# CPU_LPC1776_SUP_PROG.net
KiCad netlist of a schematic drawn in Altium Designer
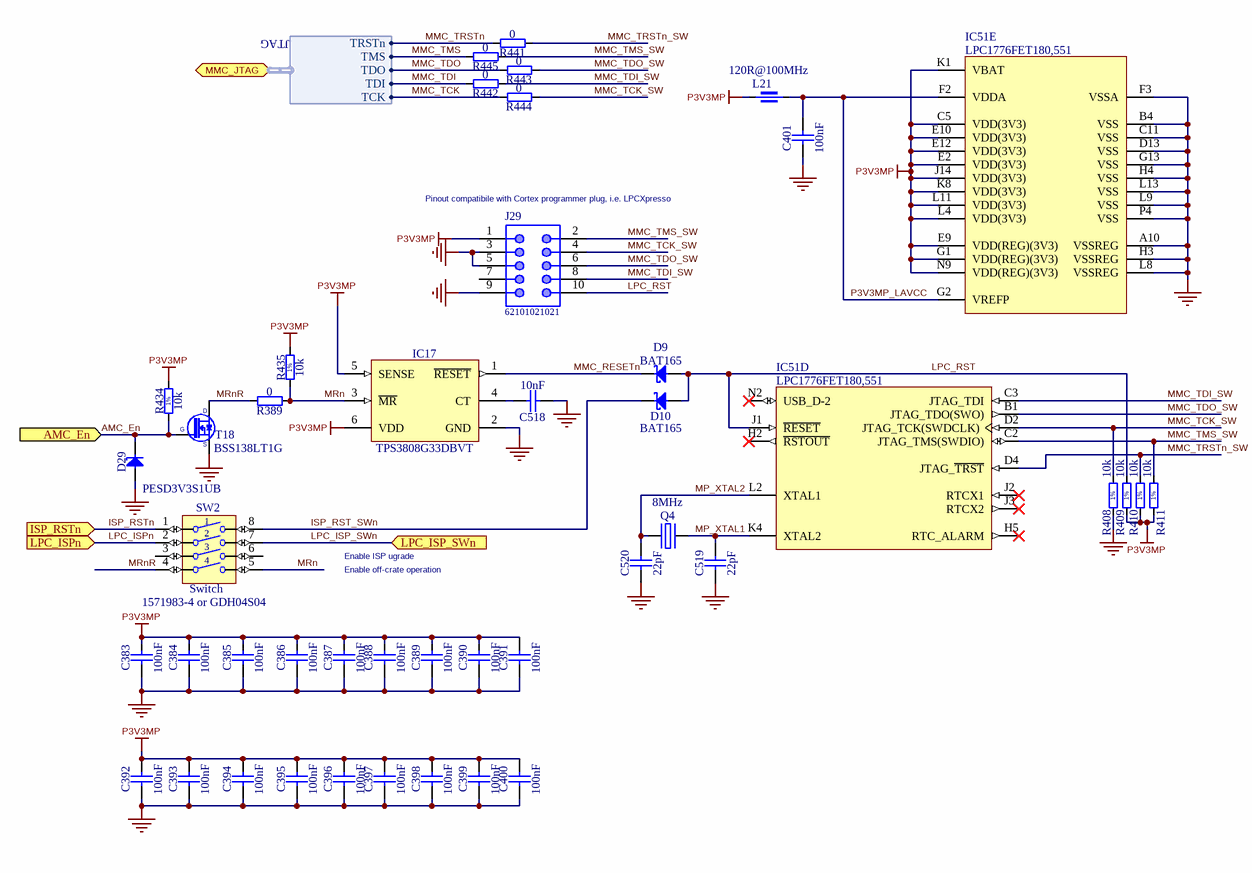
[diagram p0: CPU_LPC1776_SUP_PROG.SchDoc]

(export (version "E")
  (design (tool "Eeschema 10.0.6"))
  (components
    (comp (ref "C383")
      (value "100nF")
      (footprint "CAPC0603X33N")
      (description "Non-polarised capacitor")
      (fields
        (field (name "MANUFACTURER PART NUMBER") "CC0201_100NF_6.3V_10%_X5R")
        (field (name "MANUFACTURER") "GENERIC")
        (field (name "AUTHOR") "CERN DEM JLC")
      )
      (libsource (lib "Capacitors") (part "Capacitor - non polarized"))
    )
    (comp (ref "C384")
      (value "100nF")
      (footprint "CAPC0603X33N")
      (description "Non-polarised capacitor")
      (fields
        (field (name "MANUFACTURER PART NUMBER") "CC0201_100NF_6.3V_10%_X5R")
        (field (name "MANUFACTURER") "GENERIC")
        (field (name "AUTHOR") "CERN DEM JLC")
      )
      (libsource (lib "Capacitors") (part "Capacitor - non polarized"))
    )
    (comp (ref "C385")
      (value "100nF")
      (footprint "CAPC0603X33N")
      (description "Non-polarised capacitor")
      (fields
        (field (name "MANUFACTURER PART NUMBER") "CC0201_100NF_6.3V_10%_X5R")
        (field (name "MANUFACTURER") "GENERIC")
        (field (name "AUTHOR") "CERN DEM JLC")
      )
      (libsource (lib "Capacitors") (part "Capacitor - non polarized"))
    )
    (comp (ref "C386")
      (value "100nF")
      (footprint "CAPC0603X33N")
      (description "Non-polarised capacitor")
      (fields
        (field (name "MANUFACTURER PART NUMBER") "CC0201_100NF_6.3V_10%_X5R")
        (field (name "MANUFACTURER") "GENERIC")
        (field (name "AUTHOR") "CERN DEM JLC")
      )
      (libsource (lib "Capacitors") (part "Capacitor - non polarized"))
    )
    (comp (ref "C387")
      (value "100nF")
      (footprint "CAPC0603X33N")
      (description "Non-polarised capacitor")
      (fields
        (field (name "MANUFACTURER PART NUMBER") "CC0201_100NF_6.3V_10%_X5R")
        (field (name "MANUFACTURER") "GENERIC")
        (field (name "AUTHOR") "CERN DEM JLC")
      )
      (libsource (lib "Capacitors") (part "Capacitor - non polarized"))
    )
    (comp (ref "C388")
      (value "100nF")
      (footprint "CAPC0603X33N")
      (description "Non-polarised capacitor")
      (fields
        (field (name "MANUFACTURER PART NUMBER") "CC0201_100NF_6.3V_10%_X5R")
        (field (name "MANUFACTURER") "GENERIC")
        (field (name "AUTHOR") "CERN DEM JLC")
      )
      (libsource (lib "Capacitors") (part "Capacitor - non polarized"))
    )
    (comp (ref "C389")
      (value "100nF")
      (footprint "CAPC0603X33N")
      (description "Non-polarised capacitor")
      (fields
        (field (name "MANUFACTURER PART NUMBER") "CC0201_100NF_6.3V_10%_X5R")
        (field (name "MANUFACTURER") "GENERIC")
        (field (name "AUTHOR") "CERN DEM JLC")
      )
      (libsource (lib "Capacitors") (part "Capacitor - non polarized"))
    )
    (comp (ref "C390")
      (value "100nF")
      (footprint "CAPC0603X33N")
      (description "Non-polarised capacitor")
      (fields
        (field (name "MANUFACTURER PART NUMBER") "CC0201_100NF_6.3V_10%_X5R")
        (field (name "MANUFACTURER") "GENERIC")
        (field (name "AUTHOR") "CERN DEM JLC")
      )
      (libsource (lib "Capacitors") (part "Capacitor - non polarized"))
    )
    (comp (ref "C391")
      (value "100nF")
      (footprint "CAPC0603X33N")
      (description "Non-polarised capacitor")
      (fields
        (field (name "MANUFACTURER PART NUMBER") "CC0201_100NF_6.3V_10%_X5R")
        (field (name "MANUFACTURER") "GENERIC")
        (field (name "AUTHOR") "CERN DEM JLC")
      )
      (libsource (lib "Capacitors") (part "Capacitor - non polarized"))
    )
    (comp (ref "C392")
      (value "100nF")
      (footprint "CAPC0603X33N")
      (description "Non-polarised capacitor")
      (fields
        (field (name "MANUFACTURER PART NUMBER") "CC0201_100NF_6.3V_10%_X5R")
        (field (name "MANUFACTURER") "GENERIC")
        (field (name "AUTHOR") "CERN DEM JLC")
      )
      (libsource (lib "Capacitors") (part "Capacitor - non polarized"))
    )
    (comp (ref "C393")
      (value "100nF")
      (footprint "CAPC0603X33N")
      (description "Non-polarised capacitor")
      (fields
        (field (name "MANUFACTURER PART NUMBER") "CC0201_100NF_6.3V_10%_X5R")
        (field (name "MANUFACTURER") "GENERIC")
        (field (name "AUTHOR") "CERN DEM JLC")
      )
      (libsource (lib "Capacitors") (part "Capacitor - non polarized"))
    )
    (comp (ref "C394")
      (value "100nF")
      (footprint "CAPC0603X33N")
      (description "Non-polarised capacitor")
      (fields
        (field (name "MANUFACTURER PART NUMBER") "CC0201_100NF_6.3V_10%_X5R")
        (field (name "MANUFACTURER") "GENERIC")
        (field (name "AUTHOR") "CERN DEM JLC")
      )
      (libsource (lib "Capacitors") (part "Capacitor - non polarized"))
    )
    (comp (ref "C395")
      (value "100nF")
      (footprint "CAPC0603X33N")
      (description "Non-polarised capacitor")
      (fields
        (field (name "MANUFACTURER PART NUMBER") "CC0201_100NF_6.3V_10%_X5R")
        (field (name "MANUFACTURER") "GENERIC")
        (field (name "AUTHOR") "CERN DEM JLC")
      )
      (libsource (lib "Capacitors") (part "Capacitor - non polarized"))
    )
    (comp (ref "C396")
      (value "100nF")
      (footprint "CAPC0603X33N")
      (description "Non-polarised capacitor")
      (fields
        (field (name "MANUFACTURER PART NUMBER") "CC0201_100NF_6.3V_10%_X5R")
        (field (name "MANUFACTURER") "GENERIC")
        (field (name "AUTHOR") "CERN DEM JLC")
      )
      (libsource (lib "Capacitors") (part "Capacitor - non polarized"))
    )
    (comp (ref "C397")
      (value "100nF")
      (footprint "CAPC0603X33N")
      (description "Non-polarised capacitor")
      (fields
        (field (name "MANUFACTURER PART NUMBER") "CC0201_100NF_6.3V_10%_X5R")
        (field (name "MANUFACTURER") "GENERIC")
        (field (name "AUTHOR") "CERN DEM JLC")
      )
      (libsource (lib "Capacitors") (part "Capacitor - non polarized"))
    )
    (comp (ref "C398")
      (value "100nF")
      (footprint "CAPC0603X33N")
      (description "Non-polarised capacitor")
      (fields
        (field (name "MANUFACTURER PART NUMBER") "CC0201_100NF_6.3V_10%_X5R")
        (field (name "MANUFACTURER") "GENERIC")
        (field (name "AUTHOR") "CERN DEM JLC")
      )
      (libsource (lib "Capacitors") (part "Capacitor - non polarized"))
    )
    (comp (ref "C399")
      (value "100nF")
      (footprint "CAPC0603X33N")
      (description "Non-polarised capacitor")
      (fields
        (field (name "MANUFACTURER PART NUMBER") "CC0201_100NF_6.3V_10%_X5R")
        (field (name "MANUFACTURER") "GENERIC")
        (field (name "AUTHOR") "CERN DEM JLC")
      )
      (libsource (lib "Capacitors") (part "Capacitor - non polarized"))
    )
    (comp (ref "C400")
      (value "100nF")
      (footprint "CAPC0603X33N")
      (description "Non-polarised capacitor")
      (fields
        (field (name "MANUFACTURER PART NUMBER") "CC0201_100NF_6.3V_10%_X5R")
        (field (name "MANUFACTURER") "GENERIC")
        (field (name "AUTHOR") "CERN DEM JLC")
      )
      (libsource (lib "Capacitors") (part "Capacitor - non polarized"))
    )
    (comp (ref "C401")
      (value "100nF")
      (footprint "CAPC0603X33N")
      (description "Non-polarised capacitor")
      (fields
        (field (name "MANUFACTURER PART NUMBER") "CC0201_100NF_6.3V_10%_X5R")
        (field (name "MANUFACTURER") "GENERIC")
        (field (name "AUTHOR") "CERN DEM JLC")
      )
      (libsource (lib "Capacitors") (part "Capacitor - non polarized"))
    )
    (comp (ref "C518")
      (value "10nF")
      (footprint "CAPC1005X55N")
      (description "Non-polarised capacitor")
      (fields
        (field (name "MANUFACTURER PART NUMBER") "CC0402_10NF_16V_10%_X7R")
        (field (name "MANUFACTURER") "GENERIC")
        (field (name "AUTHOR") "CERN DEM JLC")
      )
      (libsource (lib "Capacitors") (part "Capacitor - non polarized"))
    )
    (comp (ref "C519")
      (value "22pF")
      (footprint "CAPC1005X55N")
      (description "Non-polarised capacitor")
      (fields
        (field (name "MANUFACTURER PART NUMBER") "CC0402_22PF_50V_5%_C0G")
        (field (name "MANUFACTURER") "GENERIC")
        (field (name "AUTHOR") "CERN DEM JLC")
      )
      (libsource (lib "Capacitors") (part "Capacitor - non polarized"))
    )
    (comp (ref "C520")
      (value "22pF")
      (footprint "CAPC1005X55N")
      (description "Non-polarised capacitor")
      (fields
        (field (name "MANUFACTURER PART NUMBER") "CC0402_22PF_50V_5%_C0G")
        (field (name "MANUFACTURER") "GENERIC")
        (field (name "AUTHOR") "CERN DEM JLC")
      )
      (libsource (lib "Capacitors") (part "Capacitor - non polarized"))
    )
    (comp (ref "D9")
      (value "BAT165")
      (footprint "SOD2512X110N")
      (description "Schottky Diode")
      (fields
        (field (name "MANUFACTURER") "INFINEON")
        (field (name "VOLTAGE") "40V")
        (field (name "AUTHOR") "CERN DEM JLC")
      )
      (libsource (lib "ICs And Semiconductors") (part "Diode Schottky"))
    )
    (comp (ref "D10")
      (value "BAT165")
      (footprint "SOD2512X110N")
      (description "Schottky Diode")
      (fields
        (field (name "MANUFACTURER") "INFINEON")
        (field (name "VOLTAGE") "40V")
        (field (name "AUTHOR") "CERN DEM JLC")
      )
      (libsource (lib "ICs And Semiconductors") (part "Diode Schottky"))
    )
    (comp (ref "D29")
      (value "PESD3V3S1UB")
      (footprint "SODFL1608X65N")
      (description "ESD protection diode")
      (fields
        (field (name "MANUFACTURER") "NXP SEMICONDUCTORS")
        (field (name "VOLTAGE") "3V3")
        (field (name "AUTHOR") "CERN DEM JLC")
      )
      (libsource (lib "ICs And Semiconductors") (part "Diode ESD"))
    )
    (comp (ref "IC17")
      (value "TPS3808G33DBVT")
      (footprint "SOT95P280X145-6N")
      (description "Low Quiescent Current, Programmable-Delay Supervisory Circuit")
      (fields (field (name "MANUFACTURER") "TEXAS INSTRUMENTS") (field (name "AUTHOR") "CERN DEM JLC"))
      (libsource (lib "ICs And Semiconductors") (part "TPS3808xxxDBV"))
    )
    (comp (ref "IC51")
      (value "LPC1776FET180,551")
      (footprint "BGA180C80P14X14_1200X1200X120")
      (fields (field (name "MANUFACTURER") "NXP SEMICONDUCTORS") (field (name "AUTHOR") "CERN DEM JMW"))
      (libsource (lib "ICs And Semiconductors") (part "LPC1776FET180,551"))
    )
    (comp (ref "J29")
      (value "62101021021")
      (footprint "62101021021")
      (description "SMT Vertical Pin Header WR-PHD, Pitch 1.27 mm, Dual Row, 10 pins")
      (fields (field (name "PUBLISHER") "Wurth Elektronik"))
      (libsource (lib "ALTIUM-WR-PHD_PIN_HEADER-rev18b") (part "62101021021"))
    )
    (comp (ref "L21")
      (value "120R@100MHz")
      (footprint "INDC1608X95N")
      (fields
        (field (name "MANUFACTURER PART NUMBER") "BLM18PG121SN1D")
        (field (name "MANUFACTURER") "MURATA")
        (field (name "PART NUMBER") "IND0603_MURATA_BLM18PG121SN1D")
        (field (name "AUTHOR") "CERN DEM BC")
      )
      (libsource (lib "Inductors & Transformers") (part "Ferrite Bead"))
    )
    (comp (ref "Q4")
      (value "8MHz")
      (footprint "XTAL_TXC_7A")
      (description "Quartz Crystal")
      (fields
        (field (name "MANUFACTURER PART NUMBER") "7A-8.000MAAE-T")
        (field (name "MANUFACTURER") "TXC CORPORATION")
        (field (name "AUTHOR") "CERN DEM JLC")
      )
      (libsource (lib "ICs And Semiconductors") (part "Quartz Crystal"))
    )
    (comp (ref "R389")
      (value "0")
      (footprint "RESC1005X40N")
      (description "Resistor")
      (fields
        (field (name "MANUFACTURER PART NUMBER") "R0402_0R_JUMPER")
        (field (name "MANUFACTURER") "GENERIC")
        (field (name "AUTHOR") "CERN DEM JLC")
      )
      (libsource (lib "Resistors") (part "Resistor"))
    )
    (comp (ref "R408")
      (value "10k")
      (footprint "RESC1005X40N")
      (description "Resistor - 1%")
      (fields
        (field (name "MANUFACTURER PART NUMBER") "R0402_10K_1%_0.0625W_100PPM")
        (field (name "MANUFACTURER") "GENERIC")
        (field (name "AUTHOR") "CERN DEM JLC")
      )
      (libsource (lib "Resistors") (part "Resistor - 1%"))
    )
    (comp (ref "R409")
      (value "10k")
      (footprint "RESC1005X40N")
      (description "Resistor - 1%")
      (fields
        (field (name "MANUFACTURER PART NUMBER") "R0402_10K_1%_0.0625W_100PPM")
        (field (name "MANUFACTURER") "GENERIC")
        (field (name "AUTHOR") "CERN DEM JLC")
      )
      (libsource (lib "Resistors") (part "Resistor - 1%"))
    )
    (comp (ref "R410")
      (value "10k")
      (footprint "RESC1005X40N")
      (description "Resistor - 1%")
      (fields
        (field (name "MANUFACTURER PART NUMBER") "R0402_10K_1%_0.0625W_100PPM")
        (field (name "MANUFACTURER") "GENERIC")
        (field (name "AUTHOR") "CERN DEM JLC")
      )
      (libsource (lib "Resistors") (part "Resistor - 1%"))
    )
    (comp (ref "R411")
      (value "10k")
      (footprint "RESC1005X40N")
      (description "Resistor - 1%")
      (fields
        (field (name "MANUFACTURER PART NUMBER") "R0402_10K_1%_0.0625W_100PPM")
        (field (name "MANUFACTURER") "GENERIC")
        (field (name "AUTHOR") "CERN DEM JLC")
      )
      (libsource (lib "Resistors") (part "Resistor - 1%"))
    )
    (comp (ref "R434")
      (value "10k")
      (footprint "RESC1005X40N")
      (description "Resistor - 1%")
      (fields
        (field (name "MANUFACTURER PART NUMBER") "R0402_10K_1%_0.0625W_100PPM")
        (field (name "MANUFACTURER") "GENERIC")
        (field (name "AUTHOR") "CERN DEM JLC")
      )
      (libsource (lib "Resistors") (part "Resistor - 1%"))
    )
    (comp (ref "R435")
      (value "10k")
      (footprint "RESC1005X40N")
      (description "Resistor - 1%")
      (fields
        (field (name "MANUFACTURER PART NUMBER") "R0402_10K_1%_0.0625W_100PPM")
        (field (name "MANUFACTURER") "GENERIC")
        (field (name "AUTHOR") "CERN DEM JLC")
      )
      (libsource (lib "Resistors") (part "Resistor - 1%"))
    )
    (comp (ref "R441")
      (value "0")
      (footprint "RESC1005X40N")
      (description "Resistor")
      (fields
        (field (name "MANUFACTURER PART NUMBER") "R0402_0R_JUMPER")
        (field (name "MANUFACTURER") "GENERIC")
        (field (name "AUTHOR") "CERN DEM JLC")
      )
      (libsource (lib "Resistors") (part "Resistor"))
    )
    (comp (ref "R442")
      (value "0")
      (footprint "RESC1005X40N")
      (description "Resistor")
      (fields
        (field (name "MANUFACTURER PART NUMBER") "R0402_0R_JUMPER")
        (field (name "MANUFACTURER") "GENERIC")
        (field (name "AUTHOR") "CERN DEM JLC")
      )
      (libsource (lib "Resistors") (part "Resistor"))
    )
    (comp (ref "R443")
      (value "0")
      (footprint "RESC1005X40N")
      (description "Resistor")
      (fields
        (field (name "MANUFACTURER PART NUMBER") "R0402_0R_JUMPER")
        (field (name "MANUFACTURER") "GENERIC")
        (field (name "AUTHOR") "CERN DEM JLC")
      )
      (libsource (lib "Resistors") (part "Resistor"))
    )
    (comp (ref "R444")
      (value "0")
      (footprint "RESC1005X40N")
      (description "Resistor")
      (fields
        (field (name "MANUFACTURER PART NUMBER") "R0402_0R_JUMPER")
        (field (name "MANUFACTURER") "GENERIC")
        (field (name "AUTHOR") "CERN DEM JLC")
      )
      (libsource (lib "Resistors") (part "Resistor"))
    )
    (comp (ref "R445")
      (value "0")
      (footprint "RESC1005X40N")
      (description "Resistor")
      (fields
        (field (name "MANUFACTURER PART NUMBER") "R0402_0R_JUMPER")
        (field (name "MANUFACTURER") "GENERIC")
        (field (name "AUTHOR") "CERN DEM JLC")
      )
      (libsource (lib "Resistors") (part "Resistor"))
    )
    (comp (ref "SW2")
      (value "Switch")
      (footprint "SW_TYCO_1571983-4")
      (description "4 Ways SPST DIP Switch")
      (fields
        (field (name "MANUFACTURER PART NUMBER") "1571983-4 or GDH04S04")
        (field (name "MANUFACTURER") "TYCO")
        (field (name "PART NUMBER") "SW_TYCO_1571983-4")
        (field (name "AUTHOR") "CERN DEM JLC")
      )
      (libsource (lib "Eletro-mechanical") (part "SW 4x SPST DIP Switch"))
    )
    (comp (ref "T18")
      (value "BSS138LT1G")
      (footprint "SOT95P240X110-3N")
      (description "N-CHANNEL MOSFET WITH DIODE")
      (fields (field (name "MANUFACTURER") "ON SEMICONDUCTOR") (field (name "AUTHOR") "CERN DEM JLC"))
      (libsource (lib "ICs And Semiconductors") (part "N-MOSFET-D 1G 2S 3D"))
    )
  )
  (nets
    (net (code "2") (name "/AMC_En") (class "Default")
      (node (ref "D29") (pin "1") (pinfunction "C_1") (pintype "passive"))
      (node (ref "R434") (pin "1") (pinfunction "1_1") (pintype "passive"))
      (node (ref "T18") (pin "1") (pinfunction "G_1") (pintype "passive"))
    )
    (net (code "3") (name "/ISP_RST_SWn") (class "Default")
      (node (ref "D10") (pin "1") (pinfunction "C_1") (pintype "passive"))
      (node (ref "SW2") (pin "8") (pinfunction "8_8") (pintype "bidirectional"))
    )
    (net (code "4") (name "/ISP_RSTn") (class "Default")
      (node (ref "SW2") (pin "1") (pinfunction "1_1") (pintype "bidirectional"))
    )
    (net (code "5") (name "/LPC_ISP_SWn") (class "Default")
      (node (ref "SW2") (pin "7") (pinfunction "7_7") (pintype "bidirectional"))
    )
    (net (code "6") (name "/LPC_ISPn") (class "Default")
      (node (ref "SW2") (pin "2") (pinfunction "2_2") (pintype "bidirectional"))
    )
    (net (code "7") (name "/LPC_RST") (class "Default")
      (node (ref "D10") (pin "2") (pinfunction "A_2") (pintype "passive"))
      (node (ref "D9") (pin "2") (pinfunction "A_2") (pintype "passive"))
      (node (ref "IC51") (pin "J1") (pinfunction "~{RESET}_J1") (pintype "input"))
      (node (ref "J29") (pin "10") (pinfunction "10_10") (pintype "passive"))
      (node (ref "R409") (pin "2") (pinfunction "2_2") (pintype "passive"))
    )
    (net (code "8") (name "/MMC_RESETn") (class "Default")
      (node (ref "D9") (pin "1") (pinfunction "C_1") (pintype "passive"))
      (node (ref "IC17") (pin "1") (pinfunction "~{RESET}_1") (pintype "output"))
    )
    (net (code "9") (name "/MMC_TCK") (class "Default")
      (node (ref "R444") (pin "2") (pinfunction "2_2") (pintype "passive"))
    )
    (net (code "10") (name "/MMC_TCK_SW") (class "Default")
      (node (ref "IC51") (pin "D2") (pinfunction "JTAG_TCK(SWDCLK)_D2") (pintype "input"))
      (node (ref "J29") (pin "4") (pinfunction "4_4") (pintype "passive"))
      (node (ref "R408") (pin "2") (pinfunction "2_2") (pintype "passive"))
      (node (ref "R444") (pin "1") (pinfunction "1_1") (pintype "passive"))
    )
    (net (code "11") (name "/MMC_TDI") (class "Default")
      (node (ref "R442") (pin "2") (pinfunction "2_2") (pintype "passive"))
    )
    (net (code "12") (name "/MMC_TDI_SW") (class "Default")
      (node (ref "IC51") (pin "C3") (pinfunction "JTAG_TDI_C3") (pintype "input"))
      (node (ref "J29") (pin "8") (pinfunction "8_8") (pintype "passive"))
      (node (ref "R442") (pin "1") (pinfunction "1_1") (pintype "passive"))
    )
    (net (code "13") (name "/MMC_TDO") (class "Default")
      (node (ref "R443") (pin "2") (pinfunction "2_2") (pintype "passive"))
    )
    (net (code "14") (name "/MMC_TDO_SW") (class "Default")
      (node (ref "IC51") (pin "B1") (pinfunction "JTAG_TDO(SWO)_B1") (pintype "output"))
      (node (ref "J29") (pin "6") (pinfunction "6_6") (pintype "passive"))
      (node (ref "R443") (pin "1") (pinfunction "1_1") (pintype "passive"))
    )
    (net (code "15") (name "/MMC_TMS") (class "Default")
      (node (ref "R445") (pin "2") (pinfunction "2_2") (pintype "passive"))
    )
    (net (code "16") (name "/MMC_TMS_SW") (class "Default")
      (node (ref "IC51") (pin "C2") (pinfunction "JTAG_TMS(SWDIO)_C2") (pintype "bidirectional"))
      (node (ref "J29") (pin "2") (pinfunction "2_2") (pintype "passive"))
      (node (ref "R411") (pin "2") (pinfunction "2_2") (pintype "passive"))
      (node (ref "R445") (pin "1") (pinfunction "1_1") (pintype "passive"))
    )
    (net (code "17") (name "/MMC_TRSTn") (class "Default")
      (node (ref "R441") (pin "2") (pinfunction "2_2") (pintype "passive"))
    )
    (net (code "18") (name "/MMC_TRSTn_SW") (class "Default")
      (node (ref "IC51") (pin "D4") (pinfunction "JTAG_~{TRST}_D4") (pintype "input"))
      (node (ref "R410") (pin "2") (pinfunction "2_2") (pintype "passive"))
      (node (ref "R441") (pin "1") (pinfunction "1_1") (pintype "passive"))
    )
    (net (code "19") (name "/MP_XTAL1") (class "Default")
      (node (ref "C519") (pin "2") (pinfunction "2_2") (pintype "passive"))
      (node (ref "IC51") (pin "K4") (pinfunction "XTAL2_K4") (pintype "passive"))
      (node (ref "Q4") (pin "2") (pinfunction "OSC2_2") (pintype "passive"))
    )
    (net (code "20") (name "/MP_XTAL2") (class "Default")
      (node (ref "C520") (pin "2") (pinfunction "2_2") (pintype "passive"))
      (node (ref "IC51") (pin "L2") (pinfunction "XTAL1_L2") (pintype "passive"))
      (node (ref "Q4") (pin "1") (pinfunction "OSC1_1") (pintype "passive"))
    )
    (net (code "21") (name "/MRn") (class "Default")
      (node (ref "IC17") (pin "3") (pinfunction "~{MR}_3") (pintype "input"))
      (node (ref "R389") (pin "1") (pinfunction "1_1") (pintype "passive"))
      (node (ref "R435") (pin "1") (pinfunction "1_1") (pintype "passive"))
      (node (ref "SW2") (pin "5") (pinfunction "5_5") (pintype "bidirectional"))
    )
    (net (code "22") (name "/MRnR") (class "Default")
      (node (ref "R389") (pin "2") (pinfunction "2_2") (pintype "passive"))
      (node (ref "SW2") (pin "4") (pinfunction "4_4") (pintype "bidirectional"))
      (node (ref "T18") (pin "3") (pinfunction "D_3") (pintype "passive"))
    )
    (net (code "23") (name "/P3V3MP_LAVCC") (class "Default")
      (node (ref "C401") (pin "1") (pinfunction "1_1") (pintype "passive"))
      (node (ref "IC51") (pin "F2") (pinfunction "VDDA_F2") (pintype "power_in"))
      (node (ref "IC51") (pin "G2") (pinfunction "VREFP_G2") (pintype "power_in"))
      (node (ref "L21") (pin "1") (pinfunction "1_1") (pintype "passive"))
    )
    (net (code "25") (name "GND") (class "Default")
      (node (ref "C383") (pin "2") (pinfunction "2_2") (pintype "passive"))
      (node (ref "C384") (pin "2") (pinfunction "2_2") (pintype "passive"))
      (node (ref "C385") (pin "2") (pinfunction "2_2") (pintype "passive"))
      (node (ref "C386") (pin "2") (pinfunction "2_2") (pintype "passive"))
      (node (ref "C387") (pin "2") (pinfunction "2_2") (pintype "passive"))
      (node (ref "C388") (pin "2") (pinfunction "2_2") (pintype "passive"))
      (node (ref "C389") (pin "2") (pinfunction "2_2") (pintype "passive"))
      (node (ref "C390") (pin "2") (pinfunction "2_2") (pintype "passive"))
      (node (ref "C391") (pin "2") (pinfunction "2_2") (pintype "passive"))
      (node (ref "C392") (pin "2") (pinfunction "2_2") (pintype "passive"))
      (node (ref "C393") (pin "2") (pinfunction "2_2") (pintype "passive"))
      (node (ref "C394") (pin "2") (pinfunction "2_2") (pintype "passive"))
      (node (ref "C395") (pin "2") (pinfunction "2_2") (pintype "passive"))
      (node (ref "C396") (pin "2") (pinfunction "2_2") (pintype "passive"))
      (node (ref "C397") (pin "2") (pinfunction "2_2") (pintype "passive"))
      (node (ref "C398") (pin "2") (pinfunction "2_2") (pintype "passive"))
      (node (ref "C399") (pin "2") (pinfunction "2_2") (pintype "passive"))
      (node (ref "C400") (pin "2") (pinfunction "2_2") (pintype "passive"))
      (node (ref "C401") (pin "2") (pinfunction "2_2") (pintype "passive"))
      (node (ref "C518") (pin "1") (pinfunction "1_1") (pintype "passive"))
      (node (ref "C519") (pin "1") (pinfunction "1_1") (pintype "passive"))
      (node (ref "C520") (pin "1") (pinfunction "1_1") (pintype "passive"))
      (node (ref "D29") (pin "2") (pinfunction "A_2") (pintype "passive"))
      (node (ref "IC17") (pin "2") (pinfunction "GND_2") (pintype "power_in"))
      (node (ref "IC51") (pin "A10") (pinfunction "VSSREG_A10") (pintype "power_in"))
      (node (ref "IC51") (pin "B4") (pinfunction "VSS_B4") (pintype "power_in"))
      (node (ref "IC51") (pin "C11") (pinfunction "VSS_C11") (pintype "power_in"))
      (node (ref "IC51") (pin "D13") (pinfunction "VSS_D13") (pintype "power_in"))
      (node (ref "IC51") (pin "F3") (pinfunction "VSSA_F3") (pintype "power_in"))
      (node (ref "IC51") (pin "G13") (pinfunction "VSS_G13") (pintype "power_in"))
      (node (ref "IC51") (pin "H3") (pinfunction "VSSREG_H3") (pintype "power_in"))
      (node (ref "IC51") (pin "H4") (pinfunction "VSS_H4") (pintype "power_in"))
      (node (ref "IC51") (pin "L13") (pinfunction "VSS_L13") (pintype "power_in"))
      (node (ref "IC51") (pin "L8") (pinfunction "VSSREG_L8") (pintype "power_in"))
      (node (ref "IC51") (pin "L9") (pinfunction "VSS_L9") (pintype "power_in"))
      (node (ref "IC51") (pin "P4") (pinfunction "VSS_P4") (pintype "power_in"))
      (node (ref "J29") (pin "3") (pinfunction "3_3") (pintype "passive"))
      (node (ref "J29") (pin "5") (pinfunction "5_5") (pintype "passive"))
      (node (ref "J29") (pin "9") (pinfunction "9_9") (pintype "passive"))
      (node (ref "R408") (pin "1") (pinfunction "1_1") (pintype "passive"))
      (node (ref "T18") (pin "2") (pinfunction "S_2") (pintype "passive"))
    )
    (net (code "26") (name "Net-(IC17-CT)") (class "Default")
      (node (ref "C518") (pin "2") (pinfunction "2_2") (pintype "passive"))
      (node (ref "IC17") (pin "4") (pinfunction "CT_4") (pintype "passive"))
    )
    (net (code "27") (name "P3V3MP") (class "Default")
      (node (ref "C383") (pin "1") (pinfunction "1_1") (pintype "passive"))
      (node (ref "C384") (pin "1") (pinfunction "1_1") (pintype "passive"))
      (node (ref "C385") (pin "1") (pinfunction "1_1") (pintype "passive"))
      (node (ref "C386") (pin "1") (pinfunction "1_1") (pintype "passive"))
      (node (ref "C387") (pin "1") (pinfunction "1_1") (pintype "passive"))
      (node (ref "C388") (pin "1") (pinfunction "1_1") (pintype "passive"))
      (node (ref "C389") (pin "1") (pinfunction "1_1") (pintype "passive"))
      (node (ref "C390") (pin "1") (pinfunction "1_1") (pintype "passive"))
      (node (ref "C391") (pin "1") (pinfunction "1_1") (pintype "passive"))
      (node (ref "C392") (pin "1") (pinfunction "1_1") (pintype "passive"))
      (node (ref "C393") (pin "1") (pinfunction "1_1") (pintype "passive"))
      (node (ref "C394") (pin "1") (pinfunction "1_1") (pintype "passive"))
      (node (ref "C395") (pin "1") (pinfunction "1_1") (pintype "passive"))
      (node (ref "C396") (pin "1") (pinfunction "1_1") (pintype "passive"))
      (node (ref "C397") (pin "1") (pinfunction "1_1") (pintype "passive"))
      (node (ref "C398") (pin "1") (pinfunction "1_1") (pintype "passive"))
      (node (ref "C399") (pin "1") (pinfunction "1_1") (pintype "passive"))
      (node (ref "C400") (pin "1") (pinfunction "1_1") (pintype "passive"))
      (node (ref "IC17") (pin "5") (pinfunction "SENSE_5") (pintype "input"))
      (node (ref "IC17") (pin "6") (pinfunction "VDD_6") (pintype "power_in"))
      (node (ref "IC51") (pin "C5") (pinfunction "VDD(3V3)_C5") (pintype "power_in"))
      (node (ref "IC51") (pin "E10") (pinfunction "VDD(3V3)_E10") (pintype "power_in"))
      (node (ref "IC51") (pin "E12") (pinfunction "VDD(3V3)_E12") (pintype "power_in"))
      (node (ref "IC51") (pin "E2") (pinfunction "VDD(3V3)_E2") (pintype "power_in"))
      (node (ref "IC51") (pin "E9") (pinfunction "VDD(REG)(3V3)_E9") (pintype "power_in"))
      (node (ref "IC51") (pin "G1") (pinfunction "VDD(REG)(3V3)_G1") (pintype "power_in"))
      (node (ref "IC51") (pin "J14") (pinfunction "VDD(3V3)_J14") (pintype "power_in"))
      (node (ref "IC51") (pin "K1") (pinfunction "VBAT_K1") (pintype "power_in"))
      (node (ref "IC51") (pin "K8") (pinfunction "VDD(3V3)_K8") (pintype "power_in"))
      (node (ref "IC51") (pin "L11") (pinfunction "VDD(3V3)_L11") (pintype "power_in"))
      (node (ref "IC51") (pin "L4") (pinfunction "VDD(3V3)_L4") (pintype "power_in"))
      (node (ref "IC51") (pin "N9") (pinfunction "VDD(REG)(3V3)_N9") (pintype "power_in"))
      (node (ref "J29") (pin "1") (pinfunction "1_1") (pintype "passive"))
      (node (ref "L21") (pin "2") (pinfunction "2_2") (pintype "passive"))
      (node (ref "R409") (pin "1") (pinfunction "1_1") (pintype "passive"))
      (node (ref "R410") (pin "1") (pinfunction "1_1") (pintype "passive"))
      (node (ref "R411") (pin "1") (pinfunction "1_1") (pintype "passive"))
      (node (ref "R434") (pin "2") (pinfunction "2_2") (pintype "passive"))
      (node (ref "R435") (pin "2") (pinfunction "2_2") (pintype "passive"))
    )
    (net (code "28") (name "unconnected-(IC51D-RTCX1-PadJ2)") (class "Default")
      (node (ref "IC51") (pin "J2") (pinfunction "RTCX1_J2") (pintype "input+no_connect"))
    )
    (net (code "29") (name "unconnected-(IC51D-RTCX2-PadJ3)") (class "Default")
      (node (ref "IC51") (pin "J3") (pinfunction "RTCX2_J3") (pintype "output+no_connect"))
    )
    (net (code "30") (name "unconnected-(IC51D-RTC_ALARM-PadH5)") (class "Default")
      (node (ref "IC51") (pin "H5") (pinfunction "RTC_ALARM_H5") (pintype "output+no_connect"))
    )
    (net (code "31") (name "unconnected-(IC51D-USB_D-2-PadN2)") (class "Default")
      (node (ref "IC51") (pin "N2") (pinfunction "USB_D-2_N2") (pintype "bidirectional+no_connect"))
    )
    (net (code "32") (name "unconnected-(IC51D-~{RSTOUT}-PadH2)") (class "Default")
      (node (ref "IC51") (pin "H2") (pinfunction "~{RSTOUT}_H2") (pintype "output+no_connect"))
    )
    (net (code "33") (name "unconnected-(J29-Pad7)") (class "Default")
      (node (ref "J29") (pin "7") (pinfunction "7_7") (pintype "passive"))
    )
    (net (code "34") (name "unconnected-(SW2-Pad3)") (class "Default")
      (node (ref "SW2") (pin "3") (pinfunction "3_3") (pintype "bidirectional"))
    )
    (net (code "35") (name "unconnected-(SW2-Pad6)") (class "Default")
      (node (ref "SW2") (pin "6") (pinfunction "6_6") (pintype "bidirectional"))
    )
  )
)
